# CPU_MIPI_DSI_CSI.net
KiCad netlist of a schematic drawn in Altium Designer
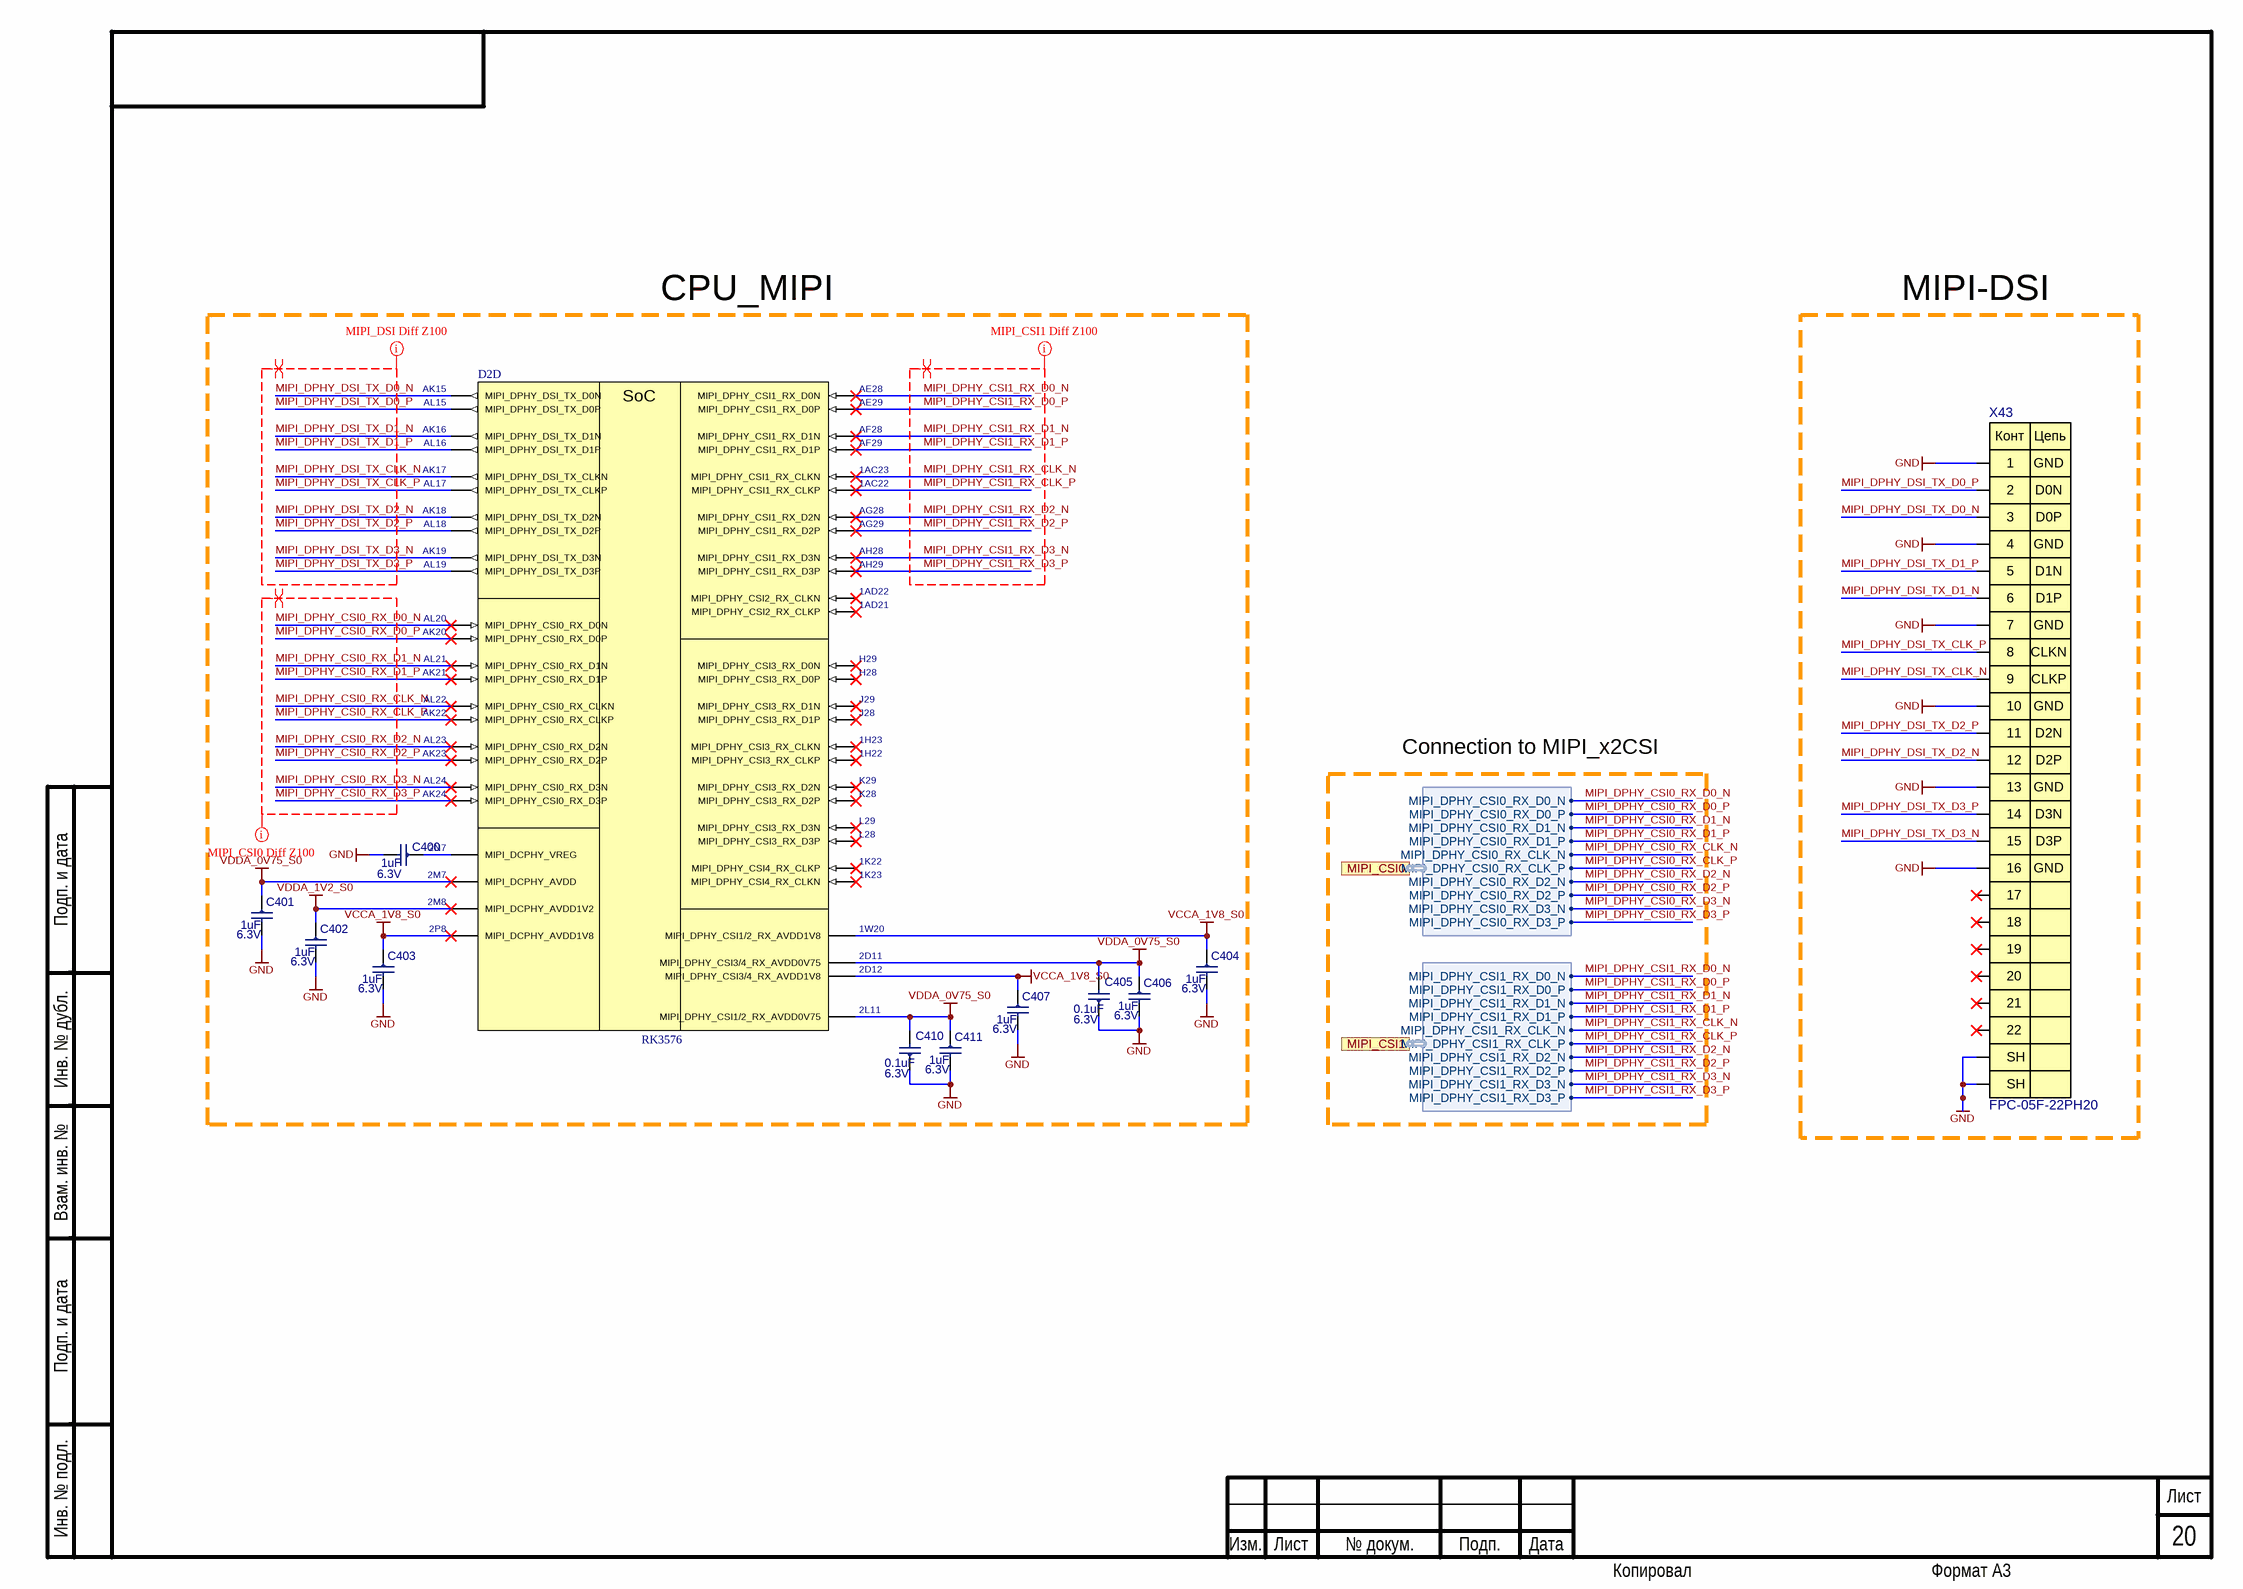
[diagram p0: CPU_MIPI_DSI_CSI.SchDoc]

(export (version "E")
  (design (tool "Eeschema 10.0.6"))
  (components
    (comp (ref "C400")
      (value "1uF")
      (footprint "C0201")
      (fields
        (field (name "VOLTAGE") "6.3V")
        (field (name "PART NUMBER") "0201-X5R-6.3V-1uF±20%")
        (field (name "TOLERANCE") "20%")
        (field (name "MANUFACTURER") "Murata Electronics")
      )
      (libsource (lib "ATB") (part "C"))
    )
    (comp (ref "C401")
      (value "1uF")
      (footprint "C0201")
      (fields
        (field (name "VOLTAGE") "6.3V")
        (field (name "PART NUMBER") "0201-X5R-6.3V-1uF±20%")
        (field (name "TOLERANCE") "20%")
        (field (name "MANUFACTURER") "Murata Electronics")
      )
      (libsource (lib "ATB") (part "C"))
    )
    (comp (ref "C402")
      (value "1uF")
      (footprint "C0201")
      (fields
        (field (name "VOLTAGE") "6.3V")
        (field (name "PART NUMBER") "0201-X5R-6.3V-1uF±20%")
        (field (name "TOLERANCE") "20%")
        (field (name "MANUFACTURER") "Murata Electronics")
      )
      (libsource (lib "ATB") (part "C"))
    )
    (comp (ref "C403")
      (value "1uF")
      (footprint "C0201")
      (fields
        (field (name "VOLTAGE") "6.3V")
        (field (name "PART NUMBER") "0201-X5R-6.3V-1uF±20%")
        (field (name "TOLERANCE") "20%")
        (field (name "MANUFACTURER") "Murata Electronics")
      )
      (libsource (lib "ATB") (part "C"))
    )
    (comp (ref "C404")
      (value "1uF")
      (footprint "C0201")
      (fields
        (field (name "VOLTAGE") "6.3V")
        (field (name "PART NUMBER") "0201-X5R-6.3V-1uF±20%")
        (field (name "TOLERANCE") "20%")
        (field (name "MANUFACTURER") "Murata Electronics")
      )
      (libsource (lib "ATB") (part "C"))
    )
    (comp (ref "C405")
      (value "0.1uF")
      (footprint "C0201")
      (fields
        (field (name "VOLTAGE") "6.3V")
        (field (name "PART NUMBER") "0201-X5R-6.3V-0.1uF±10%")
        (field (name "TOLERANCE") "10%")
        (field (name "MANUFACTURER") "Yageo")
      )
      (libsource (lib "ATB") (part "C"))
    )
    (comp (ref "C406")
      (value "1uF")
      (footprint "C0201")
      (fields
        (field (name "VOLTAGE") "6.3V")
        (field (name "PART NUMBER") "0201-X5R-6.3V-1uF±20%")
        (field (name "TOLERANCE") "20%")
        (field (name "MANUFACTURER") "Murata Electronics")
      )
      (libsource (lib "ATB") (part "C"))
    )
    (comp (ref "C407")
      (value "1uF")
      (footprint "C0201")
      (fields
        (field (name "VOLTAGE") "6.3V")
        (field (name "PART NUMBER") "0201-X5R-6.3V-1uF±20%")
        (field (name "TOLERANCE") "20%")
        (field (name "MANUFACTURER") "Murata Electronics")
      )
      (libsource (lib "ATB") (part "C"))
    )
    (comp (ref "C410")
      (value "0.1uF")
      (footprint "C0201")
      (fields
        (field (name "VOLTAGE") "6.3V")
        (field (name "PART NUMBER") "0201-X5R-6.3V-0.1uF±10%")
        (field (name "TOLERANCE") "10%")
        (field (name "MANUFACTURER") "Yageo")
      )
      (libsource (lib "ATB") (part "C"))
    )
    (comp (ref "C411")
      (value "1uF")
      (footprint "C0201")
      (fields
        (field (name "VOLTAGE") "6.3V")
        (field (name "PART NUMBER") "0201-X5R-6.3V-1uF±20%")
        (field (name "TOLERANCE") "20%")
        (field (name "MANUFACTURER") "Murata Electronics")
      )
      (libsource (lib "ATB") (part "C"))
    )
    (comp (ref "D2")
      (value "RK3576")
      (footprint "BGAFCCSP698L")
      (description "SoC 4xCortex-A72@2.2Ghz+4xCortex-A53@2Ghz, LPDDR4/4X/5/5X, SDIO/eMMC/UFS/FSPI, BGA 16.1x17.2x1.0mm")
      (fields (field (name "MANUFACTURER") "Rockship"))
      (libsource (lib "ATB") (part "RK3576"))
    )
    (comp (ref "X43")
      (value "FPC-05F-22PH20")
      (footprint "FPC-05F-22PH20")
      (description "FFC/FPC Connector 22 Position 0.5mm Pitch Bottom Contact Surface Mount, Right Angle -25℃~+85℃")
      (fields (field (name "MANUFACTURER") "XUNPU"))
      (libsource (lib "LIB_RK") (part "FPC-05F-22PH20"))
    )
  )
  (nets
    (net (code "3") (name "/MIPI_DPHY_CSI0_RX_CLK_N") (class "Default")
      (node (ref "D2") (pin "AL22") (pinfunction "MIPI_DPHY_CSI0_RX_CLKN_AL22") (pintype "input"))
    )
    (net (code "4") (name "/MIPI_DPHY_CSI0_RX_CLK_P") (class "Default")
      (node (ref "D2") (pin "AK22") (pinfunction "MIPI_DPHY_CSI0_RX_CLKP_AK22") (pintype "input"))
    )
    (net (code "5") (name "/MIPI_DPHY_CSI0_RX_D0_N") (class "Default")
      (node (ref "D2") (pin "AL20") (pinfunction "MIPI_DPHY_CSI0_RX_D0N_AL20") (pintype "input"))
    )
    (net (code "6") (name "/MIPI_DPHY_CSI0_RX_D0_P") (class "Default")
      (node (ref "D2") (pin "AK20") (pinfunction "MIPI_DPHY_CSI0_RX_D0P_AK20") (pintype "input"))
    )
    (net (code "7") (name "/MIPI_DPHY_CSI0_RX_D1_N") (class "Default")
      (node (ref "D2") (pin "AL21") (pinfunction "MIPI_DPHY_CSI0_RX_D1N_AL21") (pintype "input"))
    )
    (net (code "8") (name "/MIPI_DPHY_CSI0_RX_D1_P") (class "Default")
      (node (ref "D2") (pin "AK21") (pinfunction "MIPI_DPHY_CSI0_RX_D1P_AK21") (pintype "input"))
    )
    (net (code "9") (name "/MIPI_DPHY_CSI0_RX_D2_N") (class "Default")
      (node (ref "D2") (pin "AL23") (pinfunction "MIPI_DPHY_CSI0_RX_D2N_AL23") (pintype "input"))
    )
    (net (code "10") (name "/MIPI_DPHY_CSI0_RX_D2_P") (class "Default")
      (node (ref "D2") (pin "AK23") (pinfunction "MIPI_DPHY_CSI0_RX_D2P_AK23") (pintype "input"))
    )
    (net (code "11") (name "/MIPI_DPHY_CSI0_RX_D3_N") (class "Default")
      (node (ref "D2") (pin "AL24") (pinfunction "MIPI_DPHY_CSI0_RX_D3N_AL24") (pintype "input"))
    )
    (net (code "12") (name "/MIPI_DPHY_CSI0_RX_D3_P") (class "Default")
      (node (ref "D2") (pin "AK24") (pinfunction "MIPI_DPHY_CSI0_RX_D3P_AK24") (pintype "input"))
    )
    (net (code "13") (name "/MIPI_DPHY_CSI1_RX_CLK_N") (class "Default")
      (node (ref "D2") (pin "1AC23") (pinfunction "MIPI_DPHY_CSI1_RX_CLKN_1AC23") (pintype "input"))
    )
    (net (code "14") (name "/MIPI_DPHY_CSI1_RX_CLK_P") (class "Default")
      (node (ref "D2") (pin "1AC22") (pinfunction "MIPI_DPHY_CSI1_RX_CLKP_1AC22") (pintype "input"))
    )
    (net (code "15") (name "/MIPI_DPHY_CSI1_RX_D0_N") (class "Default")
      (node (ref "D2") (pin "AE28") (pinfunction "MIPI_DPHY_CSI1_RX_D0N_AE28") (pintype "input"))
    )
    (net (code "16") (name "/MIPI_DPHY_CSI1_RX_D0_P") (class "Default")
      (node (ref "D2") (pin "AE29") (pinfunction "MIPI_DPHY_CSI1_RX_D0P_AE29") (pintype "input"))
    )
    (net (code "17") (name "/MIPI_DPHY_CSI1_RX_D1_N") (class "Default")
      (node (ref "D2") (pin "AF28") (pinfunction "MIPI_DPHY_CSI1_RX_D1N_AF28") (pintype "input"))
    )
    (net (code "18") (name "/MIPI_DPHY_CSI1_RX_D1_P") (class "Default")
      (node (ref "D2") (pin "AF29") (pinfunction "MIPI_DPHY_CSI1_RX_D1P_AF29") (pintype "input"))
    )
    (net (code "19") (name "/MIPI_DPHY_CSI1_RX_D2_N") (class "Default")
      (node (ref "D2") (pin "AG28") (pinfunction "MIPI_DPHY_CSI1_RX_D2N_AG28") (pintype "input"))
    )
    (net (code "20") (name "/MIPI_DPHY_CSI1_RX_D2_P") (class "Default")
      (node (ref "D2") (pin "AG29") (pinfunction "MIPI_DPHY_CSI1_RX_D2P_AG29") (pintype "input"))
    )
    (net (code "21") (name "/MIPI_DPHY_CSI1_RX_D3_N") (class "Default")
      (node (ref "D2") (pin "AH28") (pinfunction "MIPI_DPHY_CSI1_RX_D3N_AH28") (pintype "input"))
    )
    (net (code "22") (name "/MIPI_DPHY_CSI1_RX_D3_P") (class "Default")
      (node (ref "D2") (pin "AH29") (pinfunction "MIPI_DPHY_CSI1_RX_D3P_AH29") (pintype "input"))
    )
    (net (code "23") (name "/MIPI_DPHY_DSI_TX_CLK_N") (class "Default")
      (node (ref "D2") (pin "AK17") (pinfunction "MIPI_DPHY_DSI_TX_CLKN_AK17") (pintype "output"))
      (node (ref "X43") (pin "9") (pinfunction "9_9") (pintype "passive"))
    )
    (net (code "24") (name "/MIPI_DPHY_DSI_TX_CLK_P") (class "Default")
      (node (ref "D2") (pin "AL17") (pinfunction "MIPI_DPHY_DSI_TX_CLKP_AL17") (pintype "output"))
      (node (ref "X43") (pin "8") (pinfunction "8_8") (pintype "passive"))
    )
    (net (code "25") (name "/MIPI_DPHY_DSI_TX_D0_N") (class "Default")
      (node (ref "D2") (pin "AK15") (pinfunction "MIPI_DPHY_DSI_TX_D0N_AK15") (pintype "output"))
      (node (ref "X43") (pin "3") (pinfunction "3_3") (pintype "passive"))
    )
    (net (code "26") (name "/MIPI_DPHY_DSI_TX_D0_P") (class "Default")
      (node (ref "D2") (pin "AL15") (pinfunction "MIPI_DPHY_DSI_TX_D0P_AL15") (pintype "output"))
      (node (ref "X43") (pin "2") (pinfunction "2_2") (pintype "passive"))
    )
    (net (code "27") (name "/MIPI_DPHY_DSI_TX_D1_N") (class "Default")
      (node (ref "D2") (pin "AK16") (pinfunction "MIPI_DPHY_DSI_TX_D1N_AK16") (pintype "output"))
      (node (ref "X43") (pin "6") (pinfunction "6_6") (pintype "passive"))
    )
    (net (code "28") (name "/MIPI_DPHY_DSI_TX_D1_P") (class "Default")
      (node (ref "D2") (pin "AL16") (pinfunction "MIPI_DPHY_DSI_TX_D1P_AL16") (pintype "output"))
      (node (ref "X43") (pin "5") (pinfunction "5_5") (pintype "passive"))
    )
    (net (code "29") (name "/MIPI_DPHY_DSI_TX_D2_N") (class "Default")
      (node (ref "D2") (pin "AK18") (pinfunction "MIPI_DPHY_DSI_TX_D2N_AK18") (pintype "output"))
      (node (ref "X43") (pin "12") (pinfunction "12_12") (pintype "passive"))
    )
    (net (code "30") (name "/MIPI_DPHY_DSI_TX_D2_P") (class "Default")
      (node (ref "D2") (pin "AL18") (pinfunction "MIPI_DPHY_DSI_TX_D2P_AL18") (pintype "output"))
      (node (ref "X43") (pin "11") (pinfunction "11_11") (pintype "passive"))
    )
    (net (code "31") (name "/MIPI_DPHY_DSI_TX_D3_N") (class "Default")
      (node (ref "D2") (pin "AK19") (pinfunction "MIPI_DPHY_DSI_TX_D3N_AK19") (pintype "output"))
      (node (ref "X43") (pin "15") (pinfunction "15_15") (pintype "passive"))
    )
    (net (code "32") (name "/MIPI_DPHY_DSI_TX_D3_P") (class "Default")
      (node (ref "D2") (pin "AL19") (pinfunction "MIPI_DPHY_DSI_TX_D3P_AL19") (pintype "output"))
      (node (ref "X43") (pin "14") (pinfunction "14_14") (pintype "passive"))
    )
    (net (code "35") (name "GND") (class "Default")
      (node (ref "C400") (pin "2") (pinfunction "2_2") (pintype "passive"))
      (node (ref "C401") (pin "2") (pinfunction "2_2") (pintype "passive"))
      (node (ref "C402") (pin "2") (pinfunction "2_2") (pintype "passive"))
      (node (ref "C403") (pin "2") (pinfunction "2_2") (pintype "passive"))
      (node (ref "C404") (pin "2") (pinfunction "2_2") (pintype "passive"))
      (node (ref "C405") (pin "1") (pinfunction "1_1") (pintype "passive"))
      (node (ref "C406") (pin "2") (pinfunction "2_2") (pintype "passive"))
      (node (ref "C407") (pin "2") (pinfunction "2_2") (pintype "passive"))
      (node (ref "C410") (pin "1") (pinfunction "1_1") (pintype "passive"))
      (node (ref "C411") (pin "2") (pinfunction "2_2") (pintype "passive"))
      (node (ref "X43") (pin "1") (pinfunction "1_1") (pintype "passive"))
      (node (ref "X43") (pin "10") (pinfunction "10_10") (pintype "passive"))
      (node (ref "X43") (pin "13") (pinfunction "13_13") (pintype "passive"))
      (node (ref "X43") (pin "16") (pinfunction "16_16") (pintype "passive"))
      (node (ref "X43") (pin "23") (pinfunction "SH_23") (pintype "passive"))
      (node (ref "X43") (pin "24") (pinfunction "SH_24") (pintype "passive"))
      (node (ref "X43") (pin "4") (pinfunction "4_4") (pintype "passive"))
      (node (ref "X43") (pin "7") (pinfunction "7_7") (pintype "passive"))
    )
    (net (code "36") (name "Net-(D2D-MIPI_DCPHY_VREG)") (class "Default")
      (node (ref "C400") (pin "1") (pinfunction "1_1") (pintype "passive"))
      (node (ref "D2") (pin "2N7") (pinfunction "MIPI_DCPHY_VREG_2N7") (pintype "open_emitter"))
    )
    (net (code "37") (name "VCCA_1V8_S0") (class "Default")
      (node (ref "C403") (pin "1") (pinfunction "1_1") (pintype "passive"))
      (node (ref "C404") (pin "1") (pinfunction "1_1") (pintype "passive"))
      (node (ref "C407") (pin "1") (pinfunction "1_1") (pintype "passive"))
      (node (ref "D2") (pin "1W20") (pinfunction "MIPI_DPHY_CSI1/2_RX_AVDD1V8_1W20") (pintype "power_in"))
      (node (ref "D2") (pin "2D12") (pinfunction "MIPI_DPHY_CSI3/4_RX_AVDD1V8_2D12") (pintype "power_in"))
      (node (ref "D2") (pin "2P8") (pinfunction "MIPI_DCPHY_AVDD1V8_2P8") (pintype "open_emitter"))
    )
    (net (code "38") (name "VDDA_0V75_S0") (class "Default")
      (node (ref "C401") (pin "1") (pinfunction "1_1") (pintype "passive"))
      (node (ref "C405") (pin "2") (pinfunction "2_2") (pintype "passive"))
      (node (ref "C406") (pin "1") (pinfunction "1_1") (pintype "passive"))
      (node (ref "C410") (pin "2") (pinfunction "2_2") (pintype "passive"))
      (node (ref "C411") (pin "1") (pinfunction "1_1") (pintype "passive"))
      (node (ref "D2") (pin "2D11") (pinfunction "MIPI_DPHY_CSI3/4_RX_AVDD0V75_2D11") (pintype "power_in"))
      (node (ref "D2") (pin "2L11") (pinfunction "MIPI_DPHY_CSI1/2_RX_AVDD0V75_2L11") (pintype "power_in"))
      (node (ref "D2") (pin "2M7") (pinfunction "MIPI_DCPHY_AVDD_2M7") (pintype "open_emitter"))
    )
    (net (code "39") (name "VDDA_1V2_S0") (class "Default")
      (node (ref "C402") (pin "1") (pinfunction "1_1") (pintype "passive"))
      (node (ref "D2") (pin "2M8") (pinfunction "MIPI_DCPHY_AVDD1V2_2M8") (pintype "open_emitter"))
    )
    (net (code "40") (name "unconnected-(D2D-MIPI_DPHY_CSI2_RX_CLKN-Pad1AD22)") (class "Default")
      (node (ref "D2") (pin "1AD22") (pinfunction "MIPI_DPHY_CSI2_RX_CLKN_1AD22") (pintype "input+no_connect"))
    )
    (net (code "41") (name "unconnected-(D2D-MIPI_DPHY_CSI2_RX_CLKP-Pad1AD21)") (class "Default")
      (node (ref "D2") (pin "1AD21") (pinfunction "MIPI_DPHY_CSI2_RX_CLKP_1AD21") (pintype "input+no_connect"))
    )
    (net (code "42") (name "unconnected-(D2D-MIPI_DPHY_CSI3_RX_CLKN-Pad1H23)") (class "Default")
      (node (ref "D2") (pin "1H23") (pinfunction "MIPI_DPHY_CSI3_RX_CLKN_1H23") (pintype "input+no_connect"))
    )
    (net (code "43") (name "unconnected-(D2D-MIPI_DPHY_CSI3_RX_CLKP-Pad1H22)") (class "Default")
      (node (ref "D2") (pin "1H22") (pinfunction "MIPI_DPHY_CSI3_RX_CLKP_1H22") (pintype "input+no_connect"))
    )
    (net (code "44") (name "unconnected-(D2D-MIPI_DPHY_CSI3_RX_D0N-PadH29)") (class "Default")
      (node (ref "D2") (pin "H29") (pinfunction "MIPI_DPHY_CSI3_RX_D0N_H29") (pintype "input+no_connect"))
    )
    (net (code "45") (name "unconnected-(D2D-MIPI_DPHY_CSI3_RX_D0P-PadH28)") (class "Default")
      (node (ref "D2") (pin "H28") (pinfunction "MIPI_DPHY_CSI3_RX_D0P_H28") (pintype "input+no_connect"))
    )
    (net (code "46") (name "unconnected-(D2D-MIPI_DPHY_CSI3_RX_D1N-PadJ29)") (class "Default")
      (node (ref "D2") (pin "J29") (pinfunction "MIPI_DPHY_CSI3_RX_D1N_J29") (pintype "input+no_connect"))
    )
    (net (code "47") (name "unconnected-(D2D-MIPI_DPHY_CSI3_RX_D1P-PadJ28)") (class "Default")
      (node (ref "D2") (pin "J28") (pinfunction "MIPI_DPHY_CSI3_RX_D1P_J28") (pintype "input+no_connect"))
    )
    (net (code "48") (name "unconnected-(D2D-MIPI_DPHY_CSI3_RX_D2N-PadK29)") (class "Default")
      (node (ref "D2") (pin "K29") (pinfunction "MIPI_DPHY_CSI3_RX_D2N_K29") (pintype "input+no_connect"))
    )
    (net (code "49") (name "unconnected-(D2D-MIPI_DPHY_CSI3_RX_D2P-PadK28)") (class "Default")
      (node (ref "D2") (pin "K28") (pinfunction "MIPI_DPHY_CSI3_RX_D2P_K28") (pintype "input+no_connect"))
    )
    (net (code "50") (name "unconnected-(D2D-MIPI_DPHY_CSI3_RX_D3N-PadL29)") (class "Default")
      (node (ref "D2") (pin "L29") (pinfunction "MIPI_DPHY_CSI3_RX_D3N_L29") (pintype "input+no_connect"))
    )
    (net (code "51") (name "unconnected-(D2D-MIPI_DPHY_CSI3_RX_D3P-PadL28)") (class "Default")
      (node (ref "D2") (pin "L28") (pinfunction "MIPI_DPHY_CSI3_RX_D3P_L28") (pintype "input+no_connect"))
    )
    (net (code "52") (name "unconnected-(D2D-MIPI_DPHY_CSI4_RX_CLKN-Pad1K23)") (class "Default")
      (node (ref "D2") (pin "1K23") (pinfunction "MIPI_DPHY_CSI4_RX_CLKN_1K23") (pintype "input+no_connect"))
    )
    (net (code "53") (name "unconnected-(D2D-MIPI_DPHY_CSI4_RX_CLKP-Pad1K22)") (class "Default")
      (node (ref "D2") (pin "1K22") (pinfunction "MIPI_DPHY_CSI4_RX_CLKP_1K22") (pintype "input+no_connect"))
    )
    (net (code "54") (name "unconnected-(X43-Pad17)") (class "Default")
      (node (ref "X43") (pin "17") (pinfunction "17_17") (pintype "passive+no_connect"))
    )
    (net (code "55") (name "unconnected-(X43-Pad18)") (class "Default")
      (node (ref "X43") (pin "18") (pinfunction "18_18") (pintype "passive+no_connect"))
    )
    (net (code "56") (name "unconnected-(X43-Pad19)") (class "Default")
      (node (ref "X43") (pin "19") (pinfunction "19_19") (pintype "passive+no_connect"))
    )
    (net (code "57") (name "unconnected-(X43-Pad20)") (class "Default")
      (node (ref "X43") (pin "20") (pinfunction "20_20") (pintype "passive+no_connect"))
    )
    (net (code "58") (name "unconnected-(X43-Pad21)") (class "Default")
      (node (ref "X43") (pin "21") (pinfunction "21_21") (pintype "passive+no_connect"))
    )
    (net (code "59") (name "unconnected-(X43-Pad22)") (class "Default")
      (node (ref "X43") (pin "22") (pinfunction "22_22") (pintype "passive+no_connect"))
    )
  )
)
